# Switches.net
KiCad netlist of a schematic drawn in Altium Designer
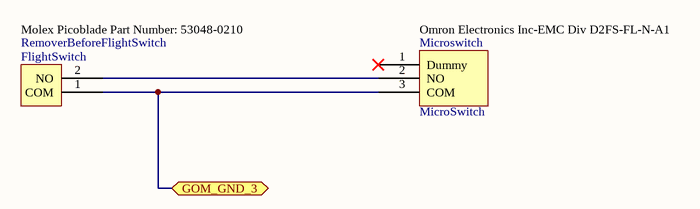
[diagram p0: Switches.SchDoc]

(export (version "E")
  (design (tool "Eeschema 10.0.6"))
  (components
    (comp (ref "FlightSwitch")
      (value "RemoverBeforeFlightSwitch")
      (footprint "UmbilicalConnectors:RemoverBeforeFlight Switch")
      (description "53048-0210 Molex Picoblade")
      (libsource (lib "UmbilicalBoardV2") (part "RemoverBeforeFlightSwitch"))
    )
    (comp (ref "Microswitch")
      (value "MicroSwitch")
      (footprint "UmbilicalConnectors:MicroSwitch_3pin")
      (description "Omron Electronics Inc-EMC Div D2FS-FL-N-A1")
      (libsource (lib "UmbilicalBoardV2") (part "MicroSwitch"))
    )
  )
  (nets
    (net (code "1") (name "/GOM_GND_3") (class "Default")
      (node (ref "FlightSwitch") (pin "1") (pinfunction "COM_1") (pintype "passive"))
      (node (ref "Microswitch") (pin "3") (pinfunction "COM_3") (pintype "passive"))
    )
    (net (code "2") (name "Net-(FlightSwitch-NO)") (class "Default")
      (node (ref "FlightSwitch") (pin "2") (pinfunction "NO_2") (pintype "passive"))
      (node (ref "Microswitch") (pin "2") (pinfunction "NO_2") (pintype "passive"))
    )
    (net (code "3") (name "unconnected-(Microswitch-Dummy-Pad1)") (class "Default")
      (node (ref "Microswitch") (pin "1") (pinfunction "Dummy_1") (pintype "passive+no_connect"))
    )
  )
)
